# fm-transmitter_v1_1.net
KiCad netlist of a schematic drawn in EAGLE
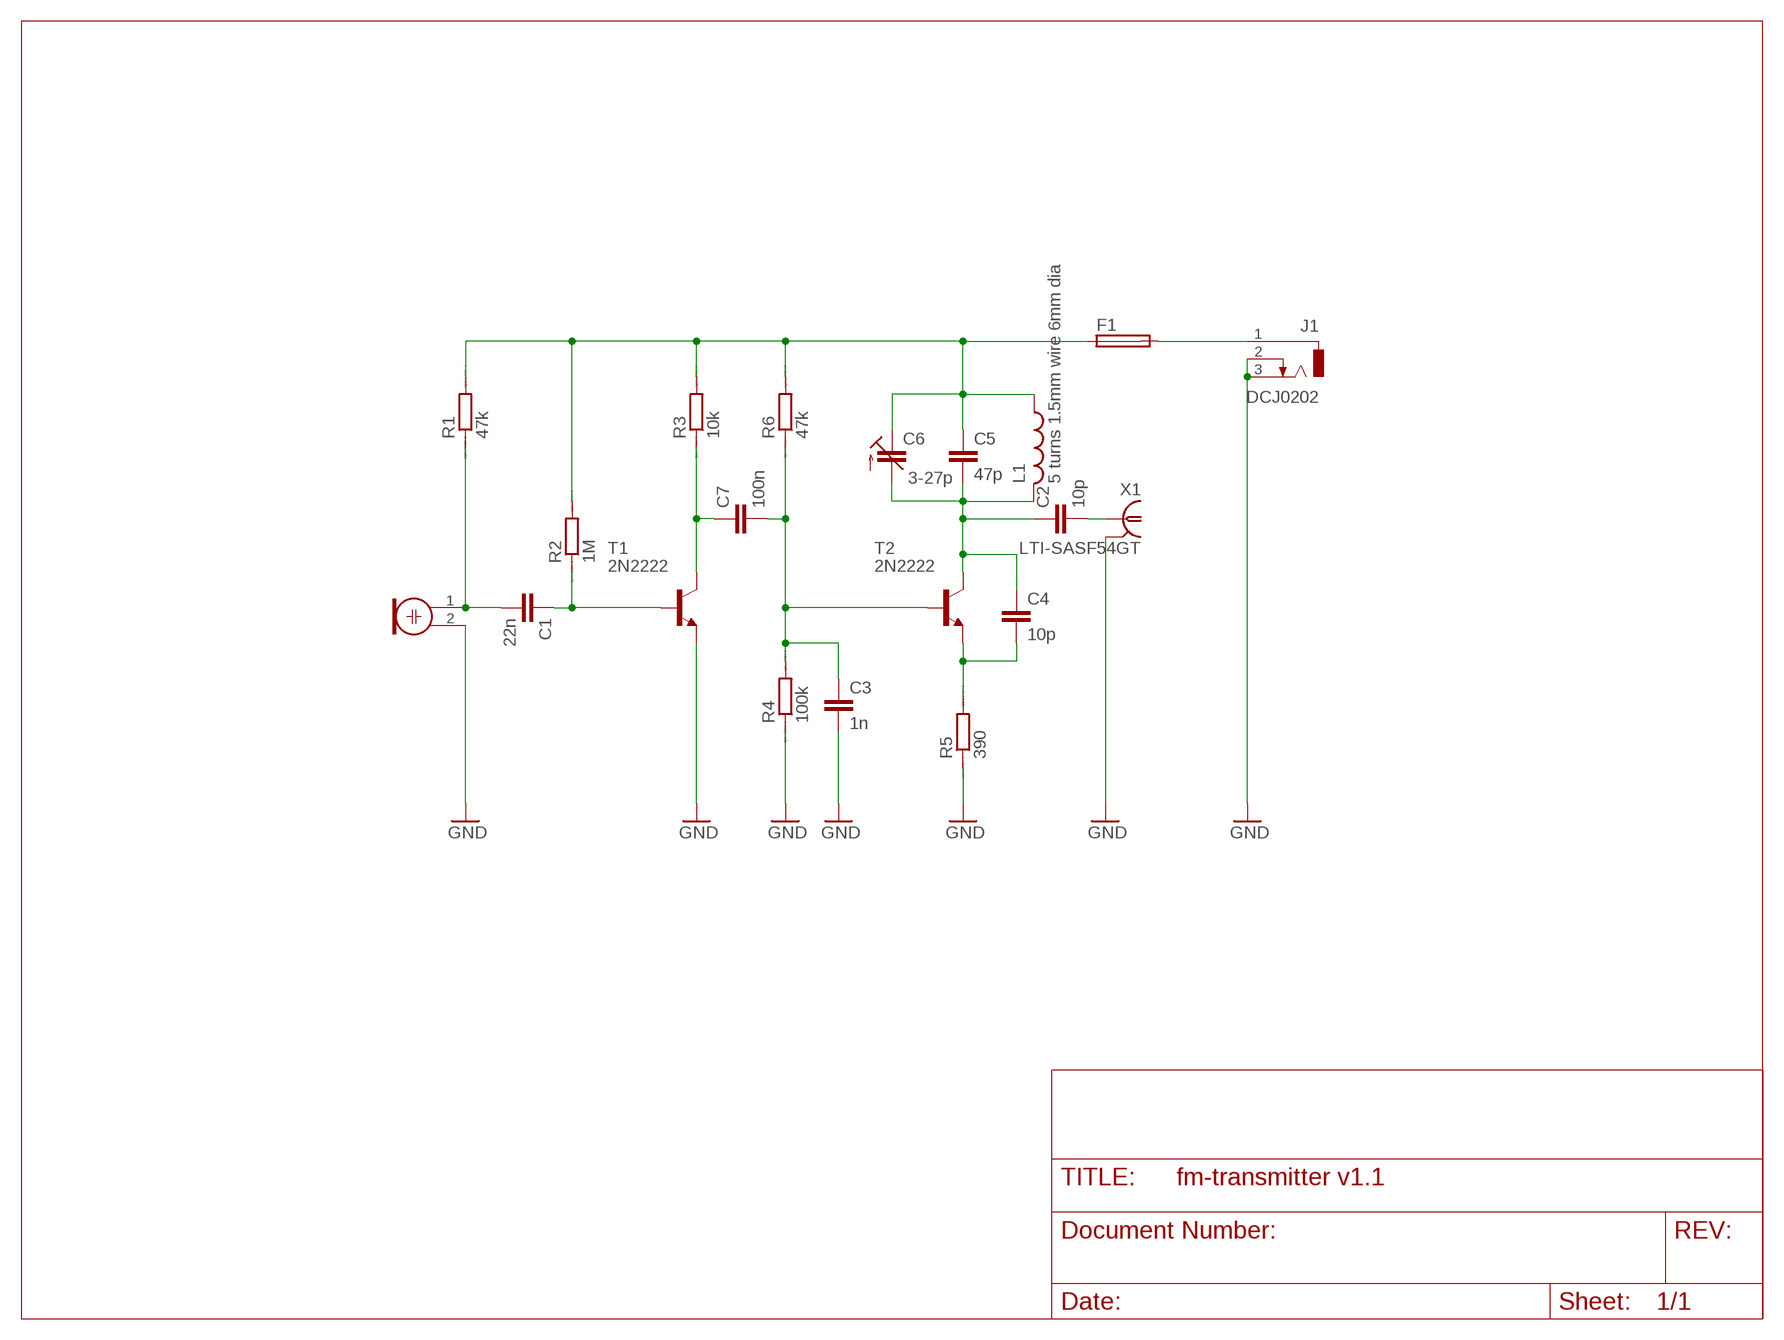
[diagram p0: schematic, sheet 1]

(export (version "E")
  (design (tool "Eeschema 10.0.6"))
  (components
    (comp (ref "C1")
      (value "22n")
      (footprint "eagle-import:C5B2.5")
      (libsource (lib "eagle-import") (part "C5/2.5"))
    )
    (comp (ref "C2")
      (value "10p")
      (footprint "eagle-import:C5B2.5")
      (libsource (lib "eagle-import") (part "C5/2.5"))
    )
    (comp (ref "C3")
      (value "1n")
      (footprint "eagle-import:C5B2.5")
      (libsource (lib "eagle-import") (part "C5/2.5"))
    )
    (comp (ref "C4")
      (value "10p")
      (footprint "eagle-import:C5B2.5")
      (libsource (lib "eagle-import") (part "C5/2.5"))
    )
    (comp (ref "C5")
      (value "47p")
      (footprint "eagle-import:C5B2.5")
      (libsource (lib "eagle-import") (part "C5/2.5"))
    )
    (comp (ref "C6")
      (value "3-27p")
      (footprint "eagle-import:CTRIM3050.504")
      (libsource (lib "eagle-import") (part "C-TRIMM3050.504"))
    )
    (comp (ref "C7")
      (value "100n")
      (footprint "eagle-import:C5B2.5")
      (libsource (lib "eagle-import") (part "C5/2.5"))
    )
    (comp (ref "F1")
      (value "TE5")
      (footprint "eagle-import:TE5")
      (libsource (lib "eagle-import") (part "TE5"))
    )
    (comp (ref "J1")
      (value "DCJ0202")
      (footprint "eagle-import:DCJ0202")
      (libsource (lib "eagle-import") (part "DCJ0202"))
    )
    (comp (ref "L1")
      (value "5 turns 1.5mm wire 6mm dia")
      (footprint "eagle-import:0207_7")
      (libsource (lib "eagle-import") (part "L-US0207/7"))
    )
    (comp (ref "M1")
      (value "ELECTRET_MICROPHON-F6050AP")
      (footprint "eagle-import:F6050AP")
      (libsource (lib "eagle-import") (part "ELECTRET_MICROPHON-F6050AP"))
    )
    (comp (ref "R1")
      (value "47k")
      (footprint "eagle-import:0207_10")
      (libsource (lib "eagle-import") (part "R0207/10"))
    )
    (comp (ref "R2")
      (value "1M")
      (footprint "eagle-import:0207_10")
      (libsource (lib "eagle-import") (part "R0207/10"))
    )
    (comp (ref "R3")
      (value "10k")
      (footprint "eagle-import:0207_10")
      (libsource (lib "eagle-import") (part "R0207/10"))
    )
    (comp (ref "R4")
      (value "100k")
      (footprint "eagle-import:0207_10")
      (libsource (lib "eagle-import") (part "R0207/10"))
    )
    (comp (ref "R5")
      (value "390")
      (footprint "eagle-import:0207_10")
      (libsource (lib "eagle-import") (part "R0207/10"))
    )
    (comp (ref "R6")
      (value "47k")
      (footprint "eagle-import:0207_10")
      (libsource (lib "eagle-import") (part "R0207/10"))
    )
    (comp (ref "T1")
      (value "2N2222")
      (footprint "eagle-import:TO18")
      (libsource (lib "eagle-import") (part "2N2222"))
    )
    (comp (ref "T2")
      (value "2N2222")
      (footprint "eagle-import:TO18")
      (libsource (lib "eagle-import") (part "2N2222"))
    )
    (comp (ref "X1")
      (value "LTI-SASF54GT")
      (footprint "eagle-import:LTI-SASF54GT")
      (libsource (lib "eagle-import") (part "LTI-SASF54GT"))
    )
  )
  (nets
    (net (code "1") (name "GND") (class "Default")
      (node (ref "C3") (pin "2") (pinfunction "2_2") (pintype "passive"))
      (node (ref "J1") (pin "2") (pinfunction "2_2") (pintype "passive"))
      (node (ref "J1") (pin "3") (pinfunction "3_3") (pintype "passive"))
      (node (ref "M1") (pin "2") (pinfunction "2_2") (pintype "passive"))
      (node (ref "R4") (pin "1") (pinfunction "1_1") (pintype "passive"))
      (node (ref "R5") (pin "1") (pinfunction "1_1") (pintype "passive"))
      (node (ref "T1") (pin "1") (pinfunction "E_1") (pintype "passive"))
      (node (ref "X1") (pin "2") (pinfunction "2_2") (pintype "passive"))
      (node (ref "X1") (pin "3") (pinfunction "2_3") (pintype "passive"))
      (node (ref "X1") (pin "4") (pinfunction "2_4") (pintype "passive"))
      (node (ref "X1") (pin "5") (pinfunction "2_5") (pintype "passive"))
    )
    (net (code "2") (name "Net-(C1-Pad2)") (class "Default")
      (node (ref "C1") (pin "2") (pinfunction "2_2") (pintype "passive"))
      (node (ref "M1") (pin "1") (pinfunction "1_1") (pintype "passive"))
      (node (ref "R1") (pin "1") (pinfunction "1_1") (pintype "passive"))
    )
    (net (code "3") (name "Net-(C2-Pad2)") (class "Default")
      (node (ref "C2") (pin "2") (pinfunction "2_2") (pintype "passive"))
      (node (ref "X1") (pin "1") (pinfunction "1_1") (pintype "passive"))
    )
    (net (code "4") (name "Net-(C6-A)") (class "Default")
      (node (ref "C2") (pin "1") (pinfunction "1_1") (pintype "passive"))
      (node (ref "C4") (pin "1") (pinfunction "1_1") (pintype "passive"))
      (node (ref "C5") (pin "2") (pinfunction "2_2") (pintype "passive"))
      (node (ref "C6") (pin "2") (pinfunction "A_2") (pintype "passive"))
      (node (ref "L1") (pin "2") (pinfunction "2_2") (pintype "passive"))
      (node (ref "T2") (pin "3") (pinfunction "C_3") (pintype "passive"))
    )
    (net (code "5") (name "Net-(C6-E)") (class "Default")
      (node (ref "C5") (pin "1") (pinfunction "1_1") (pintype "passive"))
      (node (ref "C6") (pin "1") (pinfunction "E_1") (pintype "passive"))
      (node (ref "F1") (pin "1") (pinfunction "1_1") (pintype "passive"))
      (node (ref "L1") (pin "1") (pinfunction "1_1") (pintype "passive"))
      (node (ref "R1") (pin "2") (pinfunction "2_2") (pintype "passive"))
      (node (ref "R2") (pin "2") (pinfunction "2_2") (pintype "passive"))
      (node (ref "R3") (pin "2") (pinfunction "2_2") (pintype "passive"))
      (node (ref "R6") (pin "2") (pinfunction "2_2") (pintype "passive"))
    )
    (net (code "6") (name "Net-(F1-Pad2)") (class "Default")
      (node (ref "F1") (pin "2") (pinfunction "2_2") (pintype "passive"))
      (node (ref "J1") (pin "1") (pinfunction "1_1") (pintype "passive"))
    )
    (net (code "7") (name "Net-(T1-B)") (class "Default")
      (node (ref "C1") (pin "1") (pinfunction "1_1") (pintype "passive"))
      (node (ref "R2") (pin "1") (pinfunction "1_1") (pintype "passive"))
      (node (ref "T1") (pin "2") (pinfunction "B_2") (pintype "passive"))
    )
    (net (code "8") (name "Net-(T1-C)") (class "Default")
      (node (ref "C7") (pin "1") (pinfunction "1_1") (pintype "passive"))
      (node (ref "R3") (pin "1") (pinfunction "1_1") (pintype "passive"))
      (node (ref "T1") (pin "3") (pinfunction "C_3") (pintype "passive"))
    )
    (net (code "9") (name "Net-(T2-B)") (class "Default")
      (node (ref "C3") (pin "1") (pinfunction "1_1") (pintype "passive"))
      (node (ref "C7") (pin "2") (pinfunction "2_2") (pintype "passive"))
      (node (ref "R4") (pin "2") (pinfunction "2_2") (pintype "passive"))
      (node (ref "R6") (pin "1") (pinfunction "1_1") (pintype "passive"))
      (node (ref "T2") (pin "2") (pinfunction "B_2") (pintype "passive"))
    )
    (net (code "10") (name "Net-(T2-E)") (class "Default")
      (node (ref "C4") (pin "2") (pinfunction "2_2") (pintype "passive"))
      (node (ref "R5") (pin "2") (pinfunction "2_2") (pintype "passive"))
      (node (ref "T2") (pin "1") (pinfunction "E_1") (pintype "passive"))
    )
  )
)
